# Modem_V20_5x5.net
KiCad netlist of a schematic drawn in EAGLE
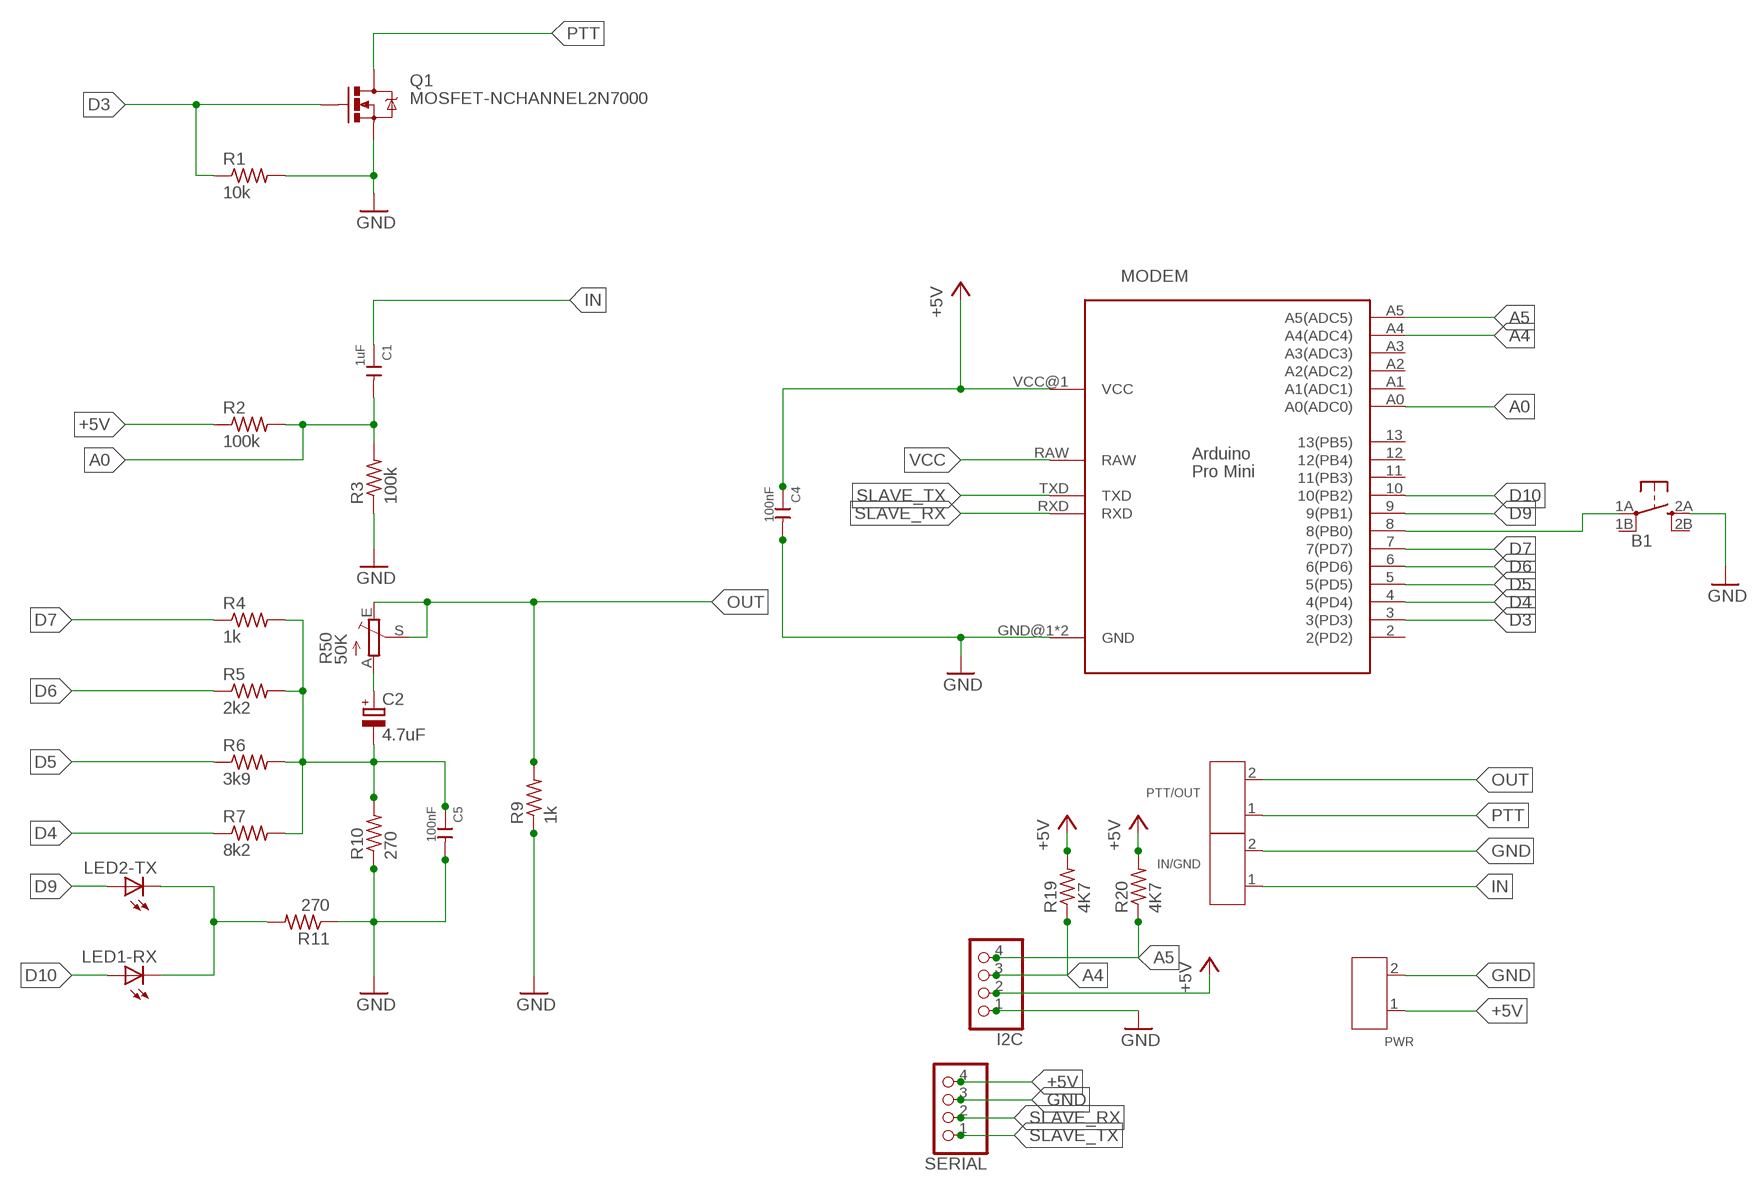
[diagram p0: schematic, sheet 1]

(export (version "E")
  (design (tool "Eeschema 10.0.6"))
  (components
    (comp (ref "B1")
      (value "TACTILETACT-6X6-PTH")
      (footprint "eagle-import:TACTILE-PTH")
      (libsource (lib "eagle-import") (part "TACTILETACT-6X6-PTH"))
    )
    (comp (ref "C1")
      (value "1uF")
      (footprint "eagle-import:C1206")
      (fields (field (name "MPN") "CC1206KKX5R8BB106"))
      (libsource (lib "eagle-import") (part "CERAMIC-10UF-25V-10%-X5R(1206)"))
    )
    (comp (ref "C2")
      (value "4.7uF")
      (footprint "eagle-import:E2,5-6")
      (libsource (lib "eagle-import") (part "CPOL-EUE2.5-6"))
    )
    (comp (ref "C4")
      (value "100nF")
      (footprint "eagle-import:C1206")
      (fields (field (name "MPN") "CC1206KKX5R8BB106"))
      (libsource (lib "eagle-import") (part "CERAMIC-10UF-25V-10%-X5R(1206)"))
    )
    (comp (ref "C5")
      (value "100nF")
      (footprint "eagle-import:C1206")
      (fields (field (name "MPN") "CC1206KKX5R8BB106"))
      (libsource (lib "eagle-import") (part "CERAMIC-10UF-25V-10%-X5R(1206)"))
    )
    (comp (ref "I2C")
      (value "PINHD-1X4")
      (footprint "eagle-import:1X04")
      (libsource (lib "eagle-import") (part "PINHD-1X4"))
    )
    (comp (ref "IN/GND")
      (value "SCREW-TERMINAL-GREEN(2P-3.5)")
      (footprint "eagle-import:H2-3.5-7.0X7.0MM")
      (libsource (lib "eagle-import") (part "SCREW-TERMINAL-GREEN(2P-3.5)"))
    )
    (comp (ref "LED1-RX")
      (value "LED1206")
      (footprint "eagle-import:LED-1206")
      (libsource (lib "eagle-import") (part "LED1206"))
    )
    (comp (ref "LED2-TX")
      (value "LED1206")
      (footprint "eagle-import:LED-1206")
      (libsource (lib "eagle-import") (part "LED1206"))
    )
    (comp (ref "MODEM")
      (value "PRO-MINI")
      (footprint "eagle-import:PRO-MINI")
      (libsource (lib "eagle-import") (part "PRO-MINI"))
    )
    (comp (ref "PTT/OUT")
      (value "SCREW-TERMINAL-GREEN(2P-3.5)")
      (footprint "eagle-import:H2-3.5-7.0X7.0MM")
      (libsource (lib "eagle-import") (part "SCREW-TERMINAL-GREEN(2P-3.5)"))
    )
    (comp (ref "PWR")
      (value "SCREW-TERMINAL-GREEN(2P-3.5)")
      (footprint "eagle-import:H2-3.5-7.0X7.0MM")
      (libsource (lib "eagle-import") (part "SCREW-TERMINAL-GREEN(2P-3.5)"))
    )
    (comp (ref "Q1")
      (value "MOSFET-NCHANNEL2N7000")
      (footprint "eagle-import:TO-92")
      (libsource (lib "eagle-import") (part "MOSFET-NCHANNEL2N7000"))
    )
    (comp (ref "R1")
      (value "10k")
      (footprint "eagle-import:R1206")
      (libsource (lib "eagle-import") (part "R-US_R1206"))
    )
    (comp (ref "R2")
      (value "100k")
      (footprint "eagle-import:R1206")
      (libsource (lib "eagle-import") (part "R-US_R1206"))
    )
    (comp (ref "R3")
      (value "100k")
      (footprint "eagle-import:R1206")
      (libsource (lib "eagle-import") (part "R-US_R1206"))
    )
    (comp (ref "R4")
      (value "1k")
      (footprint "eagle-import:R1206")
      (libsource (lib "eagle-import") (part "R-US_R1206"))
    )
    (comp (ref "R5")
      (value "2k2")
      (footprint "eagle-import:R1206")
      (libsource (lib "eagle-import") (part "R-US_R1206"))
    )
    (comp (ref "R6")
      (value "3k9")
      (footprint "eagle-import:R1206")
      (libsource (lib "eagle-import") (part "R-US_R1206"))
    )
    (comp (ref "R7")
      (value "8k2")
      (footprint "eagle-import:R1206")
      (libsource (lib "eagle-import") (part "R-US_R1206"))
    )
    (comp (ref "R9")
      (value "1k")
      (footprint "eagle-import:R1206")
      (libsource (lib "eagle-import") (part "R-US_R1206"))
    )
    (comp (ref "R10")
      (value "270")
      (footprint "eagle-import:R1206")
      (libsource (lib "eagle-import") (part "R-US_R1206"))
    )
    (comp (ref "R11")
      (value "270")
      (footprint "eagle-import:R1206")
      (libsource (lib "eagle-import") (part "R-US_R1206"))
    )
    (comp (ref "R19")
      (value "4K7")
      (footprint "eagle-import:R1206")
      (libsource (lib "eagle-import") (part "R-US_R1206"))
    )
    (comp (ref "R20")
      (value "4K7")
      (footprint "eagle-import:R1206")
      (libsource (lib "eagle-import") (part "R-US_R1206"))
    )
    (comp (ref "R50")
      (value "50K")
      (footprint "eagle-import:CA6V")
      (libsource (lib "eagle-import") (part "TRIM_EU-CA6V"))
    )
    (comp (ref "SERIAL")
      (value "PINHD-1X4")
      (footprint "eagle-import:1X04")
      (libsource (lib "eagle-import") (part "PINHD-1X4"))
    )
  )
  (nets
    (net (code "1") (name "+5V") (class "Default")
      (node (ref "C4") (pin "1") (pinfunction "1_1") (pintype "passive"))
      (node (ref "I2C") (pin "2") (pinfunction "2_2") (pintype "passive"))
      (node (ref "MODEM") (pin "VCC@1") (pinfunction "VCC_VCC@1") (pintype "bidirectional"))
      (node (ref "PWR") (pin "1") (pinfunction "1_1") (pintype "bidirectional"))
      (node (ref "R19") (pin "2") (pinfunction "2_2") (pintype "passive"))
      (node (ref "R2") (pin "1") (pinfunction "1_1") (pintype "passive"))
      (node (ref "R20") (pin "2") (pinfunction "2_2") (pintype "passive"))
      (node (ref "SERIAL") (pin "4") (pinfunction "4_4") (pintype "passive"))
    )
    (net (code "2") (name "A0") (class "Default")
      (node (ref "C1") (pin "2") (pinfunction "2_2") (pintype "passive"))
      (node (ref "MODEM") (pin "A0") (pinfunction "A0(ADC0)_A0") (pintype "bidirectional"))
      (node (ref "R2") (pin "2") (pinfunction "2_2") (pintype "passive"))
      (node (ref "R3") (pin "2") (pinfunction "2_2") (pintype "passive"))
    )
    (net (code "3") (name "A4") (class "Default")
      (node (ref "I2C") (pin "3") (pinfunction "3_3") (pintype "passive"))
      (node (ref "MODEM") (pin "A4") (pinfunction "A4(ADC4)_A4") (pintype "bidirectional"))
      (node (ref "R19") (pin "1") (pinfunction "1_1") (pintype "passive"))
    )
    (net (code "4") (name "A5") (class "Default")
      (node (ref "I2C") (pin "4") (pinfunction "4_4") (pintype "passive"))
      (node (ref "MODEM") (pin "A5") (pinfunction "A5(ADC5)_A5") (pintype "bidirectional"))
      (node (ref "R20") (pin "1") (pinfunction "1_1") (pintype "passive"))
    )
    (net (code "5") (name "D3") (class "Default")
      (node (ref "MODEM") (pin "3") (pinfunction "3(PD3)_3") (pintype "bidirectional"))
      (node (ref "Q1") (pin "2") (pinfunction "G_2") (pintype "passive"))
      (node (ref "R1") (pin "1") (pinfunction "1_1") (pintype "passive"))
    )
    (net (code "6") (name "D4") (class "Default")
      (node (ref "MODEM") (pin "4") (pinfunction "4(PD4)_4") (pintype "bidirectional"))
      (node (ref "R7") (pin "1") (pinfunction "1_1") (pintype "passive"))
    )
    (net (code "7") (name "D5") (class "Default")
      (node (ref "MODEM") (pin "5") (pinfunction "5(PD5)_5") (pintype "bidirectional"))
      (node (ref "R6") (pin "1") (pinfunction "1_1") (pintype "passive"))
    )
    (net (code "8") (name "D6") (class "Default")
      (node (ref "MODEM") (pin "6") (pinfunction "6(PD6)_6") (pintype "bidirectional"))
      (node (ref "R5") (pin "1") (pinfunction "1_1") (pintype "passive"))
    )
    (net (code "9") (name "D7") (class "Default")
      (node (ref "MODEM") (pin "7") (pinfunction "7(PD7)_7") (pintype "bidirectional"))
      (node (ref "R4") (pin "1") (pinfunction "1_1") (pintype "passive"))
    )
    (net (code "10") (name "D9") (class "Default")
      (node (ref "LED2-TX") (pin "A") (pinfunction "A_A") (pintype "passive"))
      (node (ref "MODEM") (pin "9") (pinfunction "9(PB1)_9") (pintype "bidirectional"))
    )
    (net (code "11") (name "D10") (class "Default")
      (node (ref "LED1-RX") (pin "A") (pinfunction "A_A") (pintype "passive"))
      (node (ref "MODEM") (pin "10") (pinfunction "10(PB2)_10") (pintype "bidirectional"))
    )
    (net (code "12") (name "GND") (class "Default")
      (node (ref "B1") (pin "2A") (pinfunction "2A_2A") (pintype "passive"))
      (node (ref "C4") (pin "2") (pinfunction "2_2") (pintype "passive"))
      (node (ref "C5") (pin "2") (pinfunction "2_2") (pintype "passive"))
      (node (ref "I2C") (pin "1") (pinfunction "1_1") (pintype "passive"))
      (node (ref "IN/GND") (pin "2") (pinfunction "2_2") (pintype "bidirectional"))
      (node (ref "MODEM") (pin "GND@1") (pinfunction "GND_GND@1") (pintype "bidirectional"))
      (node (ref "MODEM") (pin "GND@2") (pinfunction "GND_GND@2") (pintype "bidirectional"))
      (node (ref "PWR") (pin "2") (pinfunction "2_2") (pintype "bidirectional"))
      (node (ref "Q1") (pin "1") (pinfunction "S_1") (pintype "passive"))
      (node (ref "R1") (pin "2") (pinfunction "2_2") (pintype "passive"))
      (node (ref "R10") (pin "1") (pinfunction "1_1") (pintype "passive"))
      (node (ref "R11") (pin "1") (pinfunction "1_1") (pintype "passive"))
      (node (ref "R3") (pin "1") (pinfunction "1_1") (pintype "passive"))
      (node (ref "R9") (pin "1") (pinfunction "1_1") (pintype "passive"))
      (node (ref "SERIAL") (pin "3") (pinfunction "3_3") (pintype "passive"))
    )
    (net (code "13") (name "IN") (class "Default")
      (node (ref "C1") (pin "1") (pinfunction "1_1") (pintype "passive"))
      (node (ref "IN/GND") (pin "1") (pinfunction "1_1") (pintype "bidirectional"))
    )
    (net (code "14") (name "Net-(C2-Pad+)") (class "Default")
      (node (ref "C2") (pin "+") (pinfunction "+_+") (pintype "passive"))
      (node (ref "R50") (pin "A") (pinfunction "A_A") (pintype "passive"))
    )
    (net (code "15") (name "Net-(C2-Pad-)") (class "Default")
      (node (ref "C2") (pin "-") (pinfunction "-_-") (pintype "passive"))
      (node (ref "C5") (pin "1") (pinfunction "1_1") (pintype "passive"))
      (node (ref "R10") (pin "2") (pinfunction "2_2") (pintype "passive"))
      (node (ref "R4") (pin "2") (pinfunction "2_2") (pintype "passive"))
      (node (ref "R5") (pin "2") (pinfunction "2_2") (pintype "passive"))
      (node (ref "R6") (pin "2") (pinfunction "2_2") (pintype "passive"))
      (node (ref "R7") (pin "2") (pinfunction "2_2") (pintype "passive"))
    )
    (net (code "16") (name "Net-(LED1-RX-PadC)") (class "Default")
      (node (ref "LED1-RX") (pin "C") (pinfunction "C_C") (pintype "passive"))
      (node (ref "LED2-TX") (pin "C") (pinfunction "C_C") (pintype "passive"))
      (node (ref "R11") (pin "2") (pinfunction "2_2") (pintype "passive"))
    )
    (net (code "17") (name "Net-(MODEM-8(PB0))") (class "Default")
      (node (ref "B1") (pin "1A") (pinfunction "1A_1A") (pintype "passive"))
      (node (ref "MODEM") (pin "8") (pinfunction "8(PB0)_8") (pintype "bidirectional"))
    )
    (net (code "18") (name "OUT") (class "Default")
      (node (ref "PTT/OUT") (pin "2") (pinfunction "2_2") (pintype "bidirectional"))
      (node (ref "R50") (pin "E") (pinfunction "E_E") (pintype "passive"))
      (node (ref "R50") (pin "S") (pinfunction "S_S") (pintype "passive"))
      (node (ref "R9") (pin "2") (pinfunction "2_2") (pintype "passive"))
    )
    (net (code "19") (name "PTT") (class "Default")
      (node (ref "PTT/OUT") (pin "1") (pinfunction "1_1") (pintype "bidirectional"))
      (node (ref "Q1") (pin "3") (pinfunction "D_3") (pintype "passive"))
    )
    (net (code "20") (name "SLAVE_RX") (class "Default")
      (node (ref "MODEM") (pin "RXD") (pinfunction "RXD_RXD") (pintype "bidirectional"))
      (node (ref "SERIAL") (pin "2") (pinfunction "2_2") (pintype "passive"))
    )
    (net (code "21") (name "SLAVE_TX") (class "Default")
      (node (ref "MODEM") (pin "TXD") (pinfunction "TXD_TXD") (pintype "bidirectional"))
      (node (ref "SERIAL") (pin "1") (pinfunction "1_1") (pintype "passive"))
    )
    (net (code "22") (name "VCC") (class "Default")
      (node (ref "MODEM") (pin "RAW") (pinfunction "RAW_RAW") (pintype "bidirectional"))
    )
    (net (code "23") (name "unconnected-(B1-Pad1B)") (class "Default")
      (node (ref "B1") (pin "1B") (pinfunction "1B_1B") (pintype "passive"))
    )
    (net (code "24") (name "unconnected-(B1-Pad2B)") (class "Default")
      (node (ref "B1") (pin "2B") (pinfunction "2B_2B") (pintype "passive"))
    )
    (net (code "25") (name "unconnected-(MODEM-2(PD2)-Pad2)") (class "Default")
      (node (ref "MODEM") (pin "2") (pinfunction "2(PD2)_2") (pintype "bidirectional"))
    )
    (net (code "26") (name "unconnected-(MODEM-11(PB3)-Pad11)") (class "Default")
      (node (ref "MODEM") (pin "11") (pinfunction "11(PB3)_11") (pintype "bidirectional"))
    )
    (net (code "27") (name "unconnected-(MODEM-12(PB4)-Pad12)") (class "Default")
      (node (ref "MODEM") (pin "12") (pinfunction "12(PB4)_12") (pintype "bidirectional"))
    )
    (net (code "28") (name "unconnected-(MODEM-13(PB5)-Pad13)") (class "Default")
      (node (ref "MODEM") (pin "13") (pinfunction "13(PB5)_13") (pintype "bidirectional"))
    )
    (net (code "29") (name "unconnected-(MODEM-A1(ADC1)-PadA1)") (class "Default")
      (node (ref "MODEM") (pin "A1") (pinfunction "A1(ADC1)_A1") (pintype "bidirectional"))
    )
    (net (code "30") (name "unconnected-(MODEM-A2(ADC2)-PadA2)") (class "Default")
      (node (ref "MODEM") (pin "A2") (pinfunction "A2(ADC2)_A2") (pintype "bidirectional"))
    )
    (net (code "31") (name "unconnected-(MODEM-A3(ADC3)-PadA3)") (class "Default")
      (node (ref "MODEM") (pin "A3") (pinfunction "A3(ADC3)_A3") (pintype "bidirectional"))
    )
  )
)
